# CropSenseMovement_REV03.net
KiCad netlist of a schematic drawn in Altium Designer
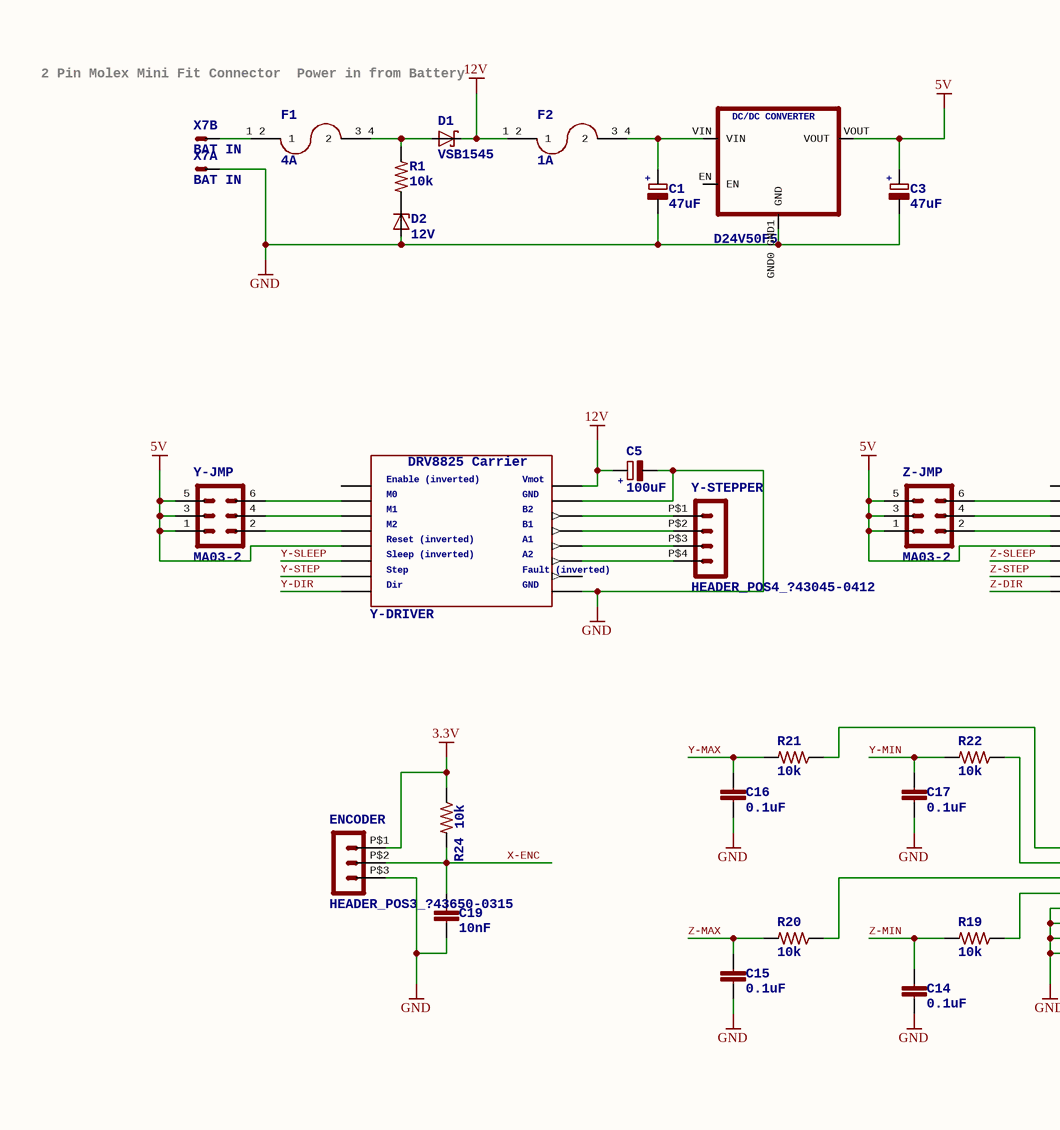
[diagram p0: CropSenseMovement_REV03.SchDoc, left]
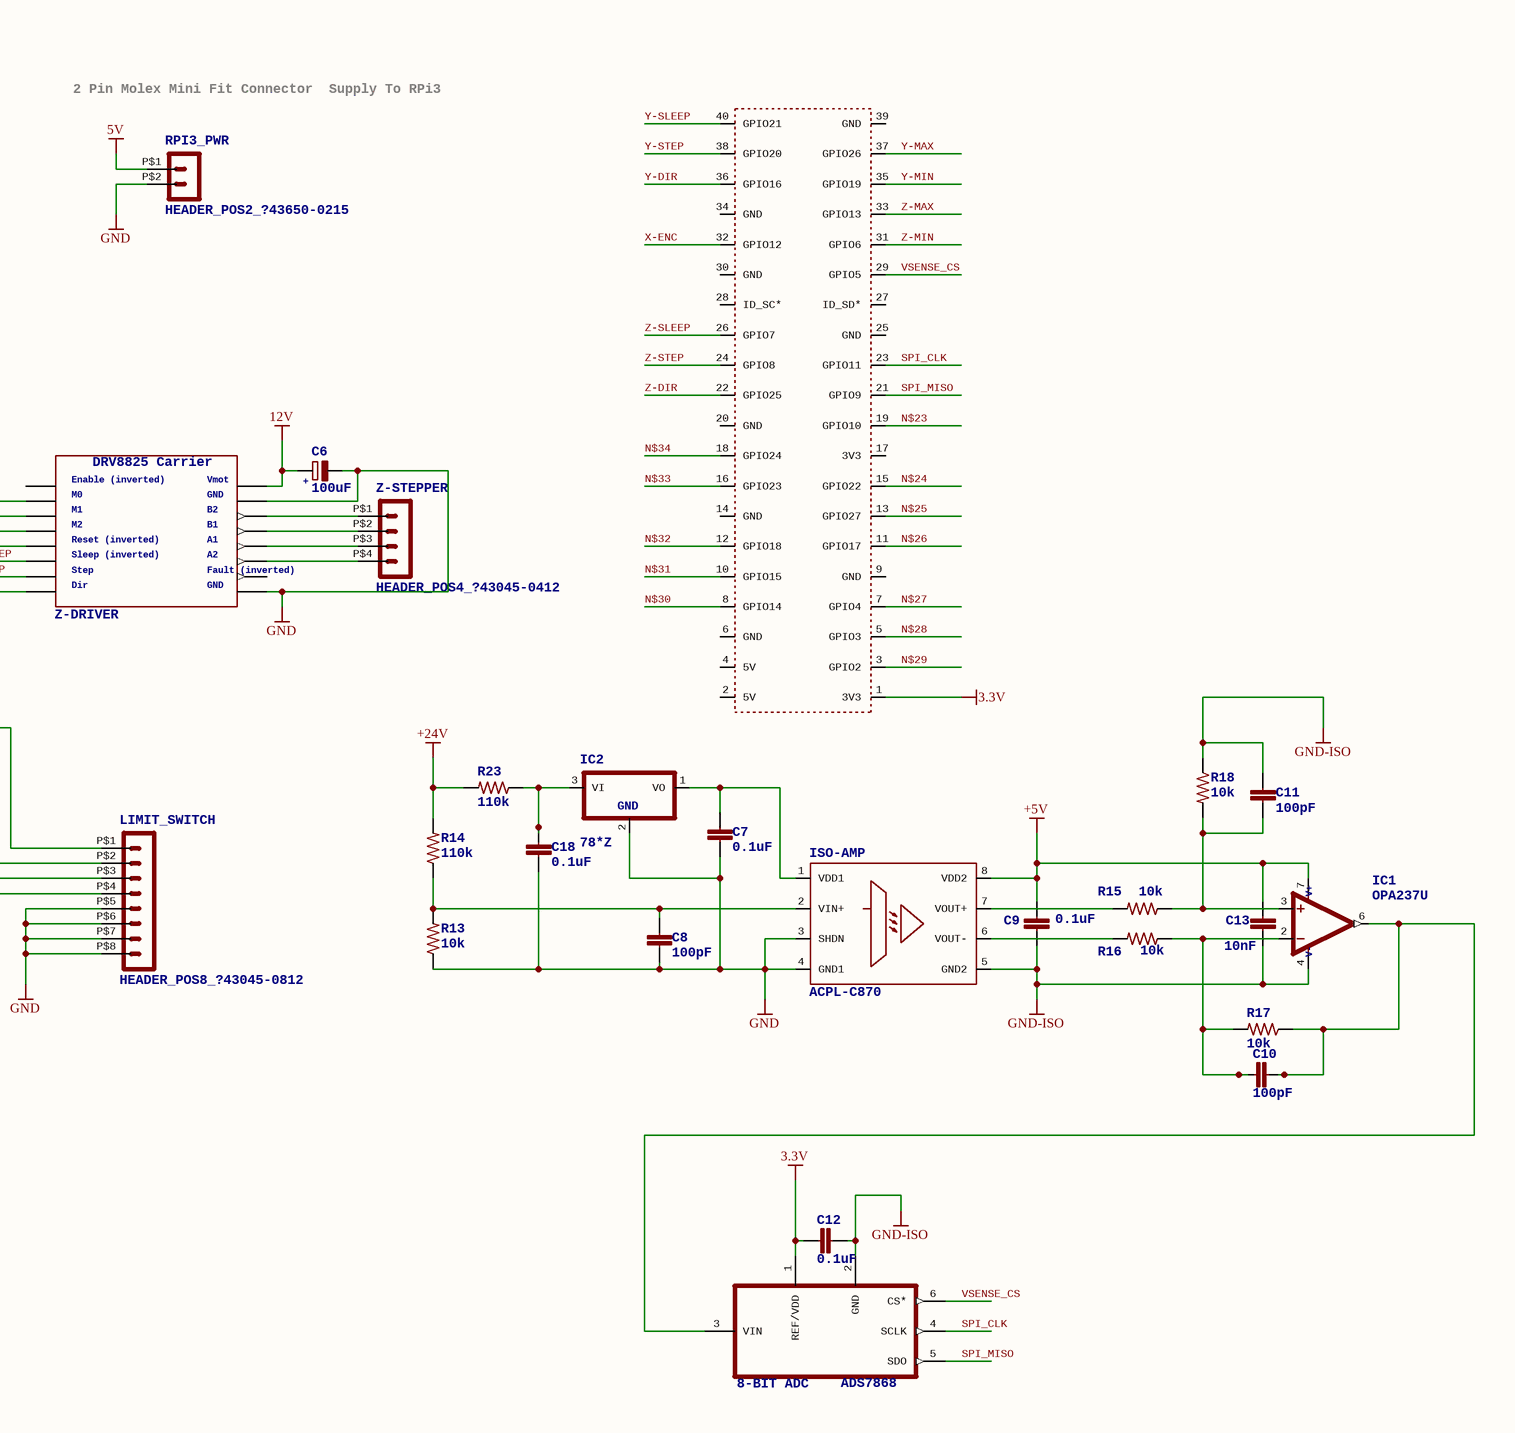
[diagram p1: CropSenseMovement_REV03.SchDoc, right]

(export (version "E")
  (design (tool "Eeschema 10.0.6"))
  (components
    (comp (ref "ADC")
      (value "ADS7868")
      (footprint "SOT-23-6")
      (description "ADS7868    8-bit ADC   Datasheet")
      (fields (field (name "8-BITADC") "8-BIT ADC"))
      (libsource (lib "ADC-BurrBrown") (part "ADS7868"))
    )
    (comp (ref "C1")
      (value "47uF")
      (footprint "E2,5-6")
      (description "POLARIZED CAPACITOR, European symbol")
      (fields (field (name "+") "+"))
      (libsource (lib "rcl") (part "CPOL-EUE2.5-6"))
    )
    (comp (ref "C3")
      (value "47uF")
      (footprint "E2,5-6")
      (description "POLARIZED CAPACITOR, European symbol")
      (fields (field (name "+") "+"))
      (libsource (lib "rcl") (part "CPOL-EUE2.5-6"))
    )
    (comp (ref "C5")
      (value "100uF")
      (footprint "PANASONIC_E")
      (description "POLARIZED CAPACITOR, European symbol")
      (fields (field (name "+") "+"))
      (libsource (lib "rcl") (part "CPOL-EUE"))
    )
    (comp (ref "C6")
      (value "100uF")
      (footprint "PANASONIC_E")
      (description "POLARIZED CAPACITOR, European symbol")
      (fields (field (name "+") "+"))
      (libsource (lib "rcl") (part "CPOL-EUE"))
    )
    (comp (ref "C7")
      (value "0.1uF")
      (footprint "C1206K")
      (description "CAPACITOR, European symbol")
      (libsource (lib "rcl") (part "C-EUC1206K"))
    )
    (comp (ref "C8")
      (value "100pF")
      (footprint "C1206K")
      (description "CAPACITOR, European symbol")
      (libsource (lib "rcl") (part "C-EUC1206K"))
    )
    (comp (ref "C9")
      (value "0.1uF")
      (footprint "C1206K")
      (description "CAPACITOR, European symbol")
      (libsource (lib "rcl") (part "C-EUC1206K"))
    )
    (comp (ref "C10")
      (value "100pF")
      (footprint "C1206K")
      (description "CAPACITOR, European symbol")
      (libsource (lib "") (part "C-EUC1206K_1"))
    )
    (comp (ref "C11")
      (value "100pF")
      (footprint "C1206K")
      (description "CAPACITOR, European symbol")
      (libsource (lib "rcl") (part "C-EUC1206K"))
    )
    (comp (ref "C12")
      (value "0.1uF")
      (footprint "C1206K")
      (description "CAPACITOR, European symbol")
      (libsource (lib "") (part "C-EUC1206K_2"))
    )
    (comp (ref "C13")
      (value "10nF")
      (footprint "C1206K")
      (description "CAPACITOR, European symbol")
      (libsource (lib "rcl") (part "C-EUC1206K"))
    )
    (comp (ref "C14")
      (value "0.1uF")
      (footprint "C1206K")
      (description "CAPACITOR, European symbol")
      (libsource (lib "rcl") (part "C-EUC1206K"))
    )
    (comp (ref "C15")
      (value "0.1uF")
      (footprint "C1206K")
      (description "CAPACITOR, European symbol")
      (libsource (lib "rcl") (part "C-EUC1206K"))
    )
    (comp (ref "C16")
      (value "0.1uF")
      (footprint "C1206K")
      (description "CAPACITOR, European symbol")
      (libsource (lib "rcl") (part "C-EUC1206K"))
    )
    (comp (ref "C17")
      (value "0.1uF")
      (footprint "C1206K")
      (description "CAPACITOR, European symbol")
      (libsource (lib "rcl") (part "C-EUC1206K"))
    )
    (comp (ref "C18")
      (value "0.1uF")
      (footprint "C1206K")
      (description "CAPACITOR, European symbol")
      (libsource (lib "rcl") (part "C-EUC1206K"))
    )
    (comp (ref "C19")
      (value "10nF")
      (footprint "C1206K")
      (description "CAPACITOR, European symbol")
      (libsource (lib "rcl") (part "C-EUC1206K"))
    )
    (comp (ref "D1")
      (value "VSB1545")
      (footprint "P6T15")
      (description "Schottky Diode")
      (libsource (lib "diode") (part "SCHOTTKY-DIODEP6T15"))
    )
    (comp (ref "D2")
      (value "12V")
      (footprint "DO35Z10")
      (description "Z-Diode")
      (libsource (lib "diode") (part "ZENER-DIODEDO35Z10"))
    )
    (comp (ref "ENCODER")
      (value "HEADER_POS3_?43650-0315")
      (footprint "43650-0315")
      (description "Molex - Micro-Fit 3.0 Series connector,  3.00mm (0.118\") pitch header, 3 positions.")
      (libsource (lib "con-molex-micro-fit-3_0") (part "HEADER_POS3_?43650-0315"))
    )
    (comp (ref "F1")
      (value "4A")
      (footprint "5X20MM_LITTLEFUSE_CARTRIDGE")
      (libsource (lib "cs-movement-custom-lib") (part "FUSE_5X20_LITTLEFUSE"))
    )
    (comp (ref "F2")
      (value "1A")
      (footprint "5X20MM_LITTLEFUSE_CARTRIDGE")
      (libsource (lib "cs-movement-custom-lib") (part "FUSE_5X20_LITTLEFUSE"))
    )
    (comp (ref "IC1")
      (value "OPA237U")
      (footprint "SO08")
      (description "Operational Amplifiers   Single-Supply, MicroAmplifier(TM) Series")
      (fields
        (field (name "MF") "TEXAS INSTRUMENT CONNECTORS")
        (field (name "MPN") "OPA237UA")
        (field (name "V+") "V+")
        (field (name "V-") "V-")
      )
      (libsource (lib "burr-brown") (part "OPA237U"))
    )
    (comp (ref "IC2")
      (value "78*Z")
      (footprint "TO92")
      (fields (field (name "GND") "GND"))
      (libsource (lib "linear") (part "78*Z"))
    )
    (comp (ref "ISO-AMP")
      (value "ACPL-C870")
      (footprint "SSO-8")
      (libsource (lib "isolated-amp-avago") (part "ACPL-C870"))
    )
    (comp (ref "LIMIT_SWITCH")
      (value "HEADER_POS8_?43045-0812")
      (footprint "43045-0812")
      (description "Molex - Micro-Fit 3.0 Series connector,  3.00mm (0.118\") pitch header, 8 positions.")
      (libsource (lib "con-molex-micro-fit-3_0") (part "HEADER_POS8_?43045-0812"))
    )
    (comp (ref "R1")
      (value "10k")
      (footprint "R1206")
      (description "RESISTOR, American symbol")
      (libsource (lib "rcl") (part "R-US_R1206"))
    )
    (comp (ref "R13")
      (value "10k")
      (footprint "R1206")
      (description "RESISTOR, American symbol")
      (libsource (lib "rcl") (part "R-US_R1206"))
    )
    (comp (ref "R14")
      (value "110k")
      (footprint "R1206")
      (description "RESISTOR, American symbol")
      (libsource (lib "rcl") (part "R-US_R1206"))
    )
    (comp (ref "R15")
      (value "10k")
      (footprint "R1206")
      (description "RESISTOR, American symbol")
      (libsource (lib "rcl") (part "R-US_R1206"))
    )
    (comp (ref "R16")
      (value "10k")
      (footprint "R1206")
      (description "RESISTOR, American symbol")
      (libsource (lib "rcl") (part "R-US_R1206"))
    )
    (comp (ref "R17")
      (value "10k")
      (footprint "R1206")
      (description "RESISTOR, American symbol")
      (libsource (lib "rcl") (part "R-US_R1206"))
    )
    (comp (ref "R18")
      (value "10k")
      (footprint "R1206")
      (description "RESISTOR, American symbol")
      (libsource (lib "rcl") (part "R-US_R1206"))
    )
    (comp (ref "R19")
      (value "10k")
      (footprint "R1206")
      (description "RESISTOR, American symbol")
      (libsource (lib "rcl") (part "R-US_R1206"))
    )
    (comp (ref "R20")
      (value "10k")
      (footprint "R1206")
      (description "RESISTOR, American symbol")
      (libsource (lib "rcl") (part "R-US_R1206"))
    )
    (comp (ref "R21")
      (value "10k")
      (footprint "R1206")
      (description "RESISTOR, American symbol")
      (libsource (lib "rcl") (part "R-US_R1206"))
    )
    (comp (ref "R22")
      (value "10k")
      (footprint "R1206")
      (description "RESISTOR, American symbol")
      (libsource (lib "rcl") (part "R-US_R1206"))
    )
    (comp (ref "R23")
      (value "110k")
      (footprint "R1206")
      (description "RESISTOR, American symbol")
      (libsource (lib "rcl") (part "R-US_R1206"))
    )
    (comp (ref "R24")
      (value "10k")
      (footprint "R1206")
      (description "RESISTOR, American symbol")
      (libsource (lib "rcl") (part "R-US_R1206"))
    )
    (comp (ref "RPI3_PWR")
      (value "HEADER_POS2_?43650-0215")
      (footprint "43650-0215")
      (description "Molex - Micro-Fit 3.0 Series connector,  3.00mm (0.118\") pitch header, 2 positions.")
      (libsource (lib "con-molex-micro-fit-3_0") (part "HEADER_POS2_?43650-0215"))
    )
    (comp (ref "U$2")
      (value "RPI3_CON")
      (footprint "CONNECTOR")
      (libsource (lib "e14_Rpi3_RevA") (part "RPI3_CON"))
    )
    (comp (ref "U$3")
      (value "D24V50F5")
      (footprint "D24VXXFX_BREAKOUT")
      (fields (field (name "DC/DCCONVERTER") "DC/DC CONVERTER"))
      (libsource (lib "cs-movement-custom-lib") (part "D24V50F5"))
    )
    (comp (ref "X7")
      (value "BAT IN")
      (footprint "5566-2")
      (description "Mini FIT connector 2 pol   Source: http://www.molex.com")
      (libsource (lib "con-molex") (part "5566-2"))
    )
    (comp (ref "Y-DRIVER")
      (value "DRV8825BREAKOUT")
      (footprint "DRV8825BREAKOUT")
      (description "DRV8825 Carrier    Datasheet")
      (fields
        (field (name "GND") "GND")
        (field (name "ENABLE(INVERTED)") "Enable (inverted)")
        (field (name "M0") "M0")
        (field (name "M1") "M1")
        (field (name "M2") "M2")
        (field (name "RESET(INVERTED)") "Reset (inverted)")
        (field (name "SLEEP(INVERTED)") "Sleep (inverted)")
        (field (name "STEP") "Step")
        (field (name "DIR") "Dir")
        (field (name "FAULT(INVERTED)") "Fault (inverted)")
        (field (name "VMOT") "Vmot")
        (field (name "GND_1") "GND")
        (field (name "B2") "B2")
        (field (name "B1") "B1")
        (field (name "A1") "A1")
        (field (name "A2") "A2")
        (field (name "DRV8825CARRIER") "DRV8825 Carrier")
      )
      (libsource (lib "RepRapjr") (part "DRV8825BREAKOUT"))
    )
    (comp (ref "Y-JMP")
      (value "MA03-2")
      (footprint "MA03-2")
      (description "PIN HEADER")
      (libsource (lib "con-lstb") (part "MA03-2"))
    )
    (comp (ref "Y-STEPPER")
      (value "HEADER_POS4_?43045-0412")
      (footprint "43045-0412")
      (description "Molex - Micro-Fit 3.0 Series connector,  3.00mm (0.118\") pitch header, 4 positions.")
      (libsource (lib "con-molex-micro-fit-3_0") (part "HEADER_POS4_?43045-0412"))
    )
    (comp (ref "Z-DRIVER")
      (value "DRV8825BREAKOUT")
      (footprint "DRV8825BREAKOUT")
      (description "DRV8825 Carrier    Datasheet")
      (fields
        (field (name "GND") "GND")
        (field (name "ENABLE(INVERTED)") "Enable (inverted)")
        (field (name "M0") "M0")
        (field (name "M1") "M1")
        (field (name "M2") "M2")
        (field (name "RESET(INVERTED)") "Reset (inverted)")
        (field (name "SLEEP(INVERTED)") "Sleep (inverted)")
        (field (name "STEP") "Step")
        (field (name "DIR") "Dir")
        (field (name "FAULT(INVERTED)") "Fault (inverted)")
        (field (name "VMOT") "Vmot")
        (field (name "GND_1") "GND")
        (field (name "B2") "B2")
        (field (name "B1") "B1")
        (field (name "A1") "A1")
        (field (name "A2") "A2")
        (field (name "DRV8825CARRIER") "DRV8825 Carrier")
      )
      (libsource (lib "RepRapjr") (part "DRV8825BREAKOUT"))
    )
    (comp (ref "Z-JMP")
      (value "MA03-2")
      (footprint "MA03-2")
      (description "PIN HEADER")
      (libsource (lib "con-lstb") (part "MA03-2"))
    )
    (comp (ref "Z-STEPPER")
      (value "HEADER_POS4_?43045-0412")
      (footprint "43045-0412")
      (description "Molex - Micro-Fit 3.0 Series connector,  3.00mm (0.118\") pitch header, 4 positions.")
      (libsource (lib "con-molex-micro-fit-3_0") (part "HEADER_POS4_?43045-0412"))
    )
  )
  (nets
    (net (code "1") (name "+5V") (class "Default")
      (node (ref "C13") (pin "1") (pinfunction "1_1") (pintype "passive"))
      (node (ref "C9") (pin "1") (pinfunction "1_1") (pintype "passive"))
      (node (ref "IC1") (pin "7") (pinfunction "V+_7") (pintype "power_in"))
      (node (ref "ISO-AMP") (pin "8") (pinfunction "VDD2_8") (pintype "power_in"))
    )
    (net (code "2") (name "+24V") (class "Default")
      (node (ref "R14") (pin "2") (pinfunction "2_2") (pintype "passive"))
      (node (ref "R23") (pin "2") (pinfunction "2_2") (pintype "passive"))
    )
    (net (code "3") (name "/N$23") (class "Default")
      (node (ref "U$2") (pin "19") (pinfunction "GPIO10_19") (pintype "passive"))
    )
    (net (code "4") (name "/N$24") (class "Default")
      (node (ref "U$2") (pin "15") (pinfunction "GPIO22_15") (pintype "passive"))
    )
    (net (code "5") (name "/N$25") (class "Default")
      (node (ref "U$2") (pin "13") (pinfunction "GPIO27_13") (pintype "passive"))
    )
    (net (code "6") (name "/N$26") (class "Default")
      (node (ref "U$2") (pin "11") (pinfunction "GPIO17_11") (pintype "passive"))
    )
    (net (code "7") (name "/N$27") (class "Default")
      (node (ref "U$2") (pin "7") (pinfunction "GPIO4_7") (pintype "passive"))
    )
    (net (code "8") (name "/N$28") (class "Default")
      (node (ref "U$2") (pin "5") (pinfunction "GPIO3_5") (pintype "passive"))
    )
    (net (code "9") (name "/N$29") (class "Default")
      (node (ref "U$2") (pin "3") (pinfunction "GPIO2_3") (pintype "passive"))
    )
    (net (code "10") (name "/N$30") (class "Default")
      (node (ref "U$2") (pin "8") (pinfunction "GPIO14_8") (pintype "passive"))
    )
    (net (code "11") (name "/N$31") (class "Default")
      (node (ref "U$2") (pin "10") (pinfunction "GPIO15_10") (pintype "passive"))
    )
    (net (code "12") (name "/N$32") (class "Default")
      (node (ref "U$2") (pin "12") (pinfunction "GPIO18_12") (pintype "passive"))
    )
    (net (code "13") (name "/N$33") (class "Default")
      (node (ref "U$2") (pin "16") (pinfunction "GPIO23_16") (pintype "passive"))
    )
    (net (code "14") (name "/N$34") (class "Default")
      (node (ref "U$2") (pin "18") (pinfunction "GPIO24_18") (pintype "passive"))
    )
    (net (code "15") (name "/SPI_CLK") (class "Default")
      (node (ref "ADC") (pin "4") (pinfunction "SCLK_4") (pintype "output"))
      (node (ref "U$2") (pin "23") (pinfunction "GPIO11_23") (pintype "passive"))
    )
    (net (code "16") (name "/SPI_MISO") (class "Default")
      (node (ref "ADC") (pin "5") (pinfunction "SDO_5") (pintype "output"))
      (node (ref "U$2") (pin "21") (pinfunction "GPIO9_21") (pintype "passive"))
    )
    (net (code "17") (name "/VSENSE_CS") (class "Default")
      (node (ref "ADC") (pin "6") (pinfunction "CS*_6") (pintype "output"))
      (node (ref "U$2") (pin "29") (pinfunction "GPIO5_29") (pintype "passive"))
    )
    (net (code "18") (name "/X-ENC") (class "Default")
      (node (ref "C19") (pin "1") (pinfunction "1_1") (pintype "passive"))
      (node (ref "ENCODER") (pin "P$2") (pinfunction "2_P$2") (pintype "passive"))
      (node (ref "R24") (pin "2") (pinfunction "2_2") (pintype "passive"))
      (node (ref "U$2") (pin "32") (pinfunction "GPIO12_32") (pintype "passive"))
    )
    (net (code "19") (name "/Y-DIR") (class "Default")
      (node (ref "U$2") (pin "36") (pinfunction "GPIO16_36") (pintype "passive"))
      (node (ref "Y-DRIVER") (pin "DIR") (pinfunction "DIR_DIR") (pintype "passive"))
    )
    (net (code "20") (name "/Y-MAX") (class "Default")
      (node (ref "C16") (pin "1") (pinfunction "1_1") (pintype "passive"))
      (node (ref "R21") (pin "2") (pinfunction "2_2") (pintype "passive"))
      (node (ref "U$2") (pin "37") (pinfunction "GPIO26_37") (pintype "passive"))
    )
    (net (code "21") (name "/Y-MIN") (class "Default")
      (node (ref "C17") (pin "1") (pinfunction "1_1") (pintype "passive"))
      (node (ref "R22") (pin "2") (pinfunction "2_2") (pintype "passive"))
      (node (ref "U$2") (pin "35") (pinfunction "GPIO19_35") (pintype "passive"))
    )
    (net (code "22") (name "/Y-SLEEP") (class "Default")
      (node (ref "U$2") (pin "40") (pinfunction "GPIO21_40") (pintype "passive"))
      (node (ref "Y-DRIVER") (pin "SLP") (pinfunction "SLEEP_SLP") (pintype "passive"))
    )
    (net (code "23") (name "/Y-STEP") (class "Default")
      (node (ref "U$2") (pin "38") (pinfunction "GPIO20_38") (pintype "passive"))
      (node (ref "Y-DRIVER") (pin "STEP") (pinfunction "STEP_STEP") (pintype "passive"))
    )
    (net (code "24") (name "/Z-DIR") (class "Default")
      (node (ref "U$2") (pin "22") (pinfunction "GPIO25_22") (pintype "passive"))
      (node (ref "Z-DRIVER") (pin "DIR") (pinfunction "DIR_DIR") (pintype "passive"))
    )
    (net (code "25") (name "/Z-MAX") (class "Default")
      (node (ref "C15") (pin "1") (pinfunction "1_1") (pintype "passive"))
      (node (ref "R20") (pin "2") (pinfunction "2_2") (pintype "passive"))
      (node (ref "U$2") (pin "33") (pinfunction "GPIO13_33") (pintype "passive"))
    )
    (net (code "26") (name "/Z-MIN") (class "Default")
      (node (ref "C14") (pin "1") (pinfunction "1_1") (pintype "passive"))
      (node (ref "R19") (pin "2") (pinfunction "2_2") (pintype "passive"))
      (node (ref "U$2") (pin "31") (pinfunction "GPIO6_31") (pintype "passive"))
    )
    (net (code "27") (name "/Z-SLEEP") (class "Default")
      (node (ref "U$2") (pin "26") (pinfunction "GPIO7_26") (pintype "passive"))
      (node (ref "Z-DRIVER") (pin "SLP") (pinfunction "SLEEP_SLP") (pintype "passive"))
    )
    (net (code "28") (name "/Z-STEP") (class "Default")
      (node (ref "U$2") (pin "24") (pinfunction "GPIO8_24") (pintype "passive"))
      (node (ref "Z-DRIVER") (pin "STEP") (pinfunction "STEP_STEP") (pintype "passive"))
    )
    (net (code "29") (name "3.3V") (class "Default")
      (node (ref "ADC") (pin "1") (pinfunction "REF/VDD_1") (pintype "power_in"))
      (node (ref "C12") (pin "1") (pinfunction "1_1") (pintype "passive"))
      (node (ref "ENCODER") (pin "P$1") (pinfunction "1_P$1") (pintype "passive"))
      (node (ref "R24") (pin "1") (pinfunction "1_1") (pintype "passive"))
      (node (ref "U$2") (pin "1") (pinfunction "3V3_1") (pintype "passive"))
    )
    (net (code "30") (name "5V") (class "Default")
      (node (ref "C3") (pin "+") (pinfunction "+_+") (pintype "passive"))
      (node (ref "RPI3_PWR") (pin "P$1") (pinfunction "1_P$1") (pintype "passive"))
      (node (ref "U$3") (pin "VOUT") (pinfunction "VOUT_VOUT") (pintype "passive"))
      (node (ref "Y-DRIVER") (pin "RST") (pinfunction "RST_RST") (pintype "passive"))
      (node (ref "Y-JMP") (pin "1") (pinfunction "1_1") (pintype "passive"))
      (node (ref "Y-JMP") (pin "3") (pinfunction "3_3") (pintype "passive"))
      (node (ref "Y-JMP") (pin "5") (pinfunction "5_5") (pintype "passive"))
      (node (ref "Z-DRIVER") (pin "RST") (pinfunction "RST_RST") (pintype "passive"))
      (node (ref "Z-JMP") (pin "1") (pinfunction "1_1") (pintype "passive"))
      (node (ref "Z-JMP") (pin "3") (pinfunction "3_3") (pintype "passive"))
      (node (ref "Z-JMP") (pin "5") (pinfunction "5_5") (pintype "passive"))
    )
    (net (code "31") (name "12V") (class "Default")
      (node (ref "C5") (pin "+") (pinfunction "+_+") (pintype "passive"))
      (node (ref "C6") (pin "+") (pinfunction "+_+") (pintype "passive"))
      (node (ref "D1") (pin "C") (pinfunction "C_C") (pintype "passive"))
      (node (ref "F2") (pin "1_2") (pinfunction "1_1_2") (pintype "passive"))
      (node (ref "Y-DRIVER") (pin "VMOT") (pinfunction "VMOT_VMOT") (pintype "power_in"))
      (node (ref "Z-DRIVER") (pin "VMOT") (pinfunction "VMOT_VMOT") (pintype "power_in"))
    )
    (net (code "32") (name "GND") (class "Default")
      (node (ref "C1") (pin "-") (pinfunction "-_-") (pintype "passive"))
      (node (ref "C14") (pin "2") (pinfunction "2_2") (pintype "passive"))
      (node (ref "C15") (pin "2") (pinfunction "2_2") (pintype "passive"))
      (node (ref "C16") (pin "2") (pinfunction "2_2") (pintype "passive"))
      (node (ref "C17") (pin "2") (pinfunction "2_2") (pintype "passive"))
      (node (ref "C18") (pin "2") (pinfunction "2_2") (pintype "passive"))
      (node (ref "C19") (pin "2") (pinfunction "2_2") (pintype "passive"))
      (node (ref "C3") (pin "-") (pinfunction "-_-") (pintype "passive"))
      (node (ref "C5") (pin "-") (pinfunction "-_-") (pintype "passive"))
      (node (ref "C6") (pin "-") (pinfunction "-_-") (pintype "passive"))
      (node (ref "C7") (pin "2") (pinfunction "2_2") (pintype "passive"))
      (node (ref "C8") (pin "2") (pinfunction "2_2") (pintype "passive"))
      (node (ref "D2") (pin "A") (pinfunction "A_A") (pintype "passive"))
      (node (ref "ENCODER") (pin "P$3") (pinfunction "3_P$3") (pintype "passive"))
      (node (ref "IC2") (pin "2") (pinfunction "GND_2") (pintype "passive"))
      (node (ref "ISO-AMP") (pin "3") (pinfunction "SHDN_3") (pintype "power_in"))
      (node (ref "ISO-AMP") (pin "4") (pinfunction "GND1_4") (pintype "power_in"))
      (node (ref "LIMIT_SWITCH") (pin "P$5") (pinfunction "5_P$5") (pintype "passive"))
      (node (ref "LIMIT_SWITCH") (pin "P$6") (pinfunction "6_P$6") (pintype "passive"))
      (node (ref "LIMIT_SWITCH") (pin "P$7") (pinfunction "7_P$7") (pintype "passive"))
      (node (ref "LIMIT_SWITCH") (pin "P$8") (pinfunction "8_P$8") (pintype "passive"))
      (node (ref "R13") (pin "1") (pinfunction "1_1") (pintype "passive"))
      (node (ref "RPI3_PWR") (pin "P$2") (pinfunction "2_P$2") (pintype "passive"))
      (node (ref "U$3") (pin "GND0_GND1") (pinfunction "GND_GND0_GND1") (pintype "passive"))
      (node (ref "X7") (pin "1") (pinfunction "S_1") (pintype "passive"))
      (node (ref "Y-DRIVER") (pin "GND") (pinfunction "GND_GND") (pintype "power_in"))
      (node (ref "Y-DRIVER") (pin "GND0") (pinfunction "GND0_GND0") (pintype "power_in"))
      (node (ref "Z-DRIVER") (pin "GND") (pinfunction "GND_GND") (pintype "power_in"))
      (node (ref "Z-DRIVER") (pin "GND0") (pinfunction "GND0_GND0") (pintype "power_in"))
    )
    (net (code "33") (name "GND-ISO") (class "Default")
      (node (ref "ADC") (pin "2") (pinfunction "GND_2") (pintype "power_in"))
      (node (ref "C11") (pin "1") (pinfunction "1_1") (pintype "passive"))
      (node (ref "C12") (pin "2") (pinfunction "2_2") (pintype "passive"))
      (node (ref "C13") (pin "2") (pinfunction "2_2") (pintype "passive"))
      (node (ref "C9") (pin "2") (pinfunction "2_2") (pintype "passive"))
      (node (ref "IC1") (pin "4") (pinfunction "V-_4") (pintype "power_in"))
      (node (ref "ISO-AMP") (pin "5") (pinfunction "GND2_5") (pintype "power_in"))
      (node (ref "R18") (pin "1") (pinfunction "1_1") (pintype "passive"))
    )
    (net (code "34") (name "Net-(ADC-VIN)") (class "Default")
      (node (ref "ADC") (pin "3") (pinfunction "VIN_3") (pintype "passive"))
      (node (ref "C10") (pin "1") (pinfunction "1_1") (pintype "passive"))
      (node (ref "IC1") (pin "6") (pinfunction "OUT_6") (pintype "output"))
      (node (ref "R17") (pin "1") (pinfunction "1_1") (pintype "passive"))
    )
    (net (code "35") (name "Net-(D2-PadC)") (class "Default")
      (node (ref "D2") (pin "C") (pinfunction "C_C") (pintype "passive"))
      (node (ref "R1") (pin "2") (pinfunction "2_2") (pintype "passive"))
    )
    (net (code "36") (name "Net-(F1-1)") (class "Default")
      (node (ref "F1") (pin "1_2") (pinfunction "1_1_2") (pintype "passive"))
      (node (ref "X7") (pin "2") (pinfunction "S_2") (pintype "passive"))
    )
    (net (code "37") (name "Net-(F1-2)") (class "Default")
      (node (ref "D1") (pin "A") (pinfunction "A_A") (pintype "passive"))
      (node (ref "F1") (pin "3_4") (pinfunction "2_3_4") (pintype "passive"))
      (node (ref "R1") (pin "1") (pinfunction "1_1") (pintype "passive"))
    )
    (net (code "38") (name "Net-(F2-2)") (class "Default")
      (node (ref "C1") (pin "+") (pinfunction "+_+") (pintype "passive"))
      (node (ref "F2") (pin "3_4") (pinfunction "2_3_4") (pintype "passive"))
      (node (ref "U$3") (pin "VIN") (pinfunction "VIN_VIN") (pintype "passive"))
    )
    (net (code "39") (name "Net-(IC1-+IN)") (class "Default")
      (node (ref "C11") (pin "2") (pinfunction "2_2") (pintype "passive"))
      (node (ref "IC1") (pin "3") (pinfunction "+IN_3") (pintype "passive"))
      (node (ref "R15") (pin "1") (pinfunction "1_1") (pintype "passive"))
      (node (ref "R18") (pin "2") (pinfunction "2_2") (pintype "passive"))
    )
    (net (code "40") (name "Net-(IC1--IN)") (class "Default")
      (node (ref "C10") (pin "2") (pinfunction "2_2") (pintype "passive"))
      (node (ref "IC1") (pin "2") (pinfunction "-IN_2") (pintype "passive"))
      (node (ref "R16") (pin "1") (pinfunction "1_1") (pintype "passive"))
      (node (ref "R17") (pin "2") (pinfunction "2_2") (pintype "passive"))
    )
    (net (code "41") (name "Net-(IC2-VI)") (class "Default")
      (node (ref "C18") (pin "1") (pinfunction "1_1") (pintype "passive"))
      (node (ref "IC2") (pin "3") (pinfunction "VI_3") (pintype "passive"))
      (node (ref "R23") (pin "1") (pinfunction "1_1") (pintype "passive"))
    )
    (net (code "42") (name "Net-(IC2-VO)") (class "Default")
      (node (ref "C7") (pin "1") (pinfunction "1_1") (pintype "passive"))
      (node (ref "IC2") (pin "1") (pinfunction "VO_1") (pintype "passive"))
      (node (ref "ISO-AMP") (pin "1") (pinfunction "VDD1_1") (pintype "power_in"))
    )
    (net (code "43") (name "Net-(ISO-AMP-VIN+)") (class "Default")
      (node (ref "C8") (pin "1") (pinfunction "1_1") (pintype "passive"))
      (node (ref "ISO-AMP") (pin "2") (pinfunction "VIN+_2") (pintype "power_in"))
      (node (ref "R13") (pin "2") (pinfunction "2_2") (pintype "passive"))
      (node (ref "R14") (pin "1") (pinfunction "1_1") (pintype "passive"))
    )
    (net (code "44") (name "Net-(ISO-AMP-VOUT+)") (class "Default")
      (node (ref "ISO-AMP") (pin "7") (pinfunction "VOUT+_7") (pintype "power_in"))
      (node (ref "R15") (pin "2") (pinfunction "2_2") (pintype "passive"))
    )
    (net (code "45") (name "Net-(ISO-AMP-VOUT-)") (class "Default")
      (node (ref "ISO-AMP") (pin "6") (pinfunction "VOUT-_6") (pintype "power_in"))
      (node (ref "R16") (pin "2") (pinfunction "2_2") (pintype "passive"))
    )
    (net (code "46") (name "Net-(LIMIT_SWITCH-1)") (class "Default")
      (node (ref "LIMIT_SWITCH") (pin "P$1") (pinfunction "1_P$1") (pintype "passive"))
      (node (ref "R21") (pin "1") (pinfunction "1_1") (pintype "passive"))
    )
    (net (code "47") (name "Net-(LIMIT_SWITCH-2)") (class "Default")
      (node (ref "LIMIT_SWITCH") (pin "P$2") (pinfunction "2_P$2") (pintype "passive"))
      (node (ref "R22") (pin "1") (pinfunction "1_1") (pintype "passive"))
    )
    (net (code "48") (name "Net-(LIMIT_SWITCH-3)") (class "Default")
      (node (ref "LIMIT_SWITCH") (pin "P$3") (pinfunction "3_P$3") (pintype "passive"))
      (node (ref "R20") (pin "1") (pinfunction "1_1") (pintype "passive"))
    )
    (net (code "49") (name "Net-(LIMIT_SWITCH-4)") (class "Default")
      (node (ref "LIMIT_SWITCH") (pin "P$4") (pinfunction "4_P$4") (pintype "passive"))
      (node (ref "R19") (pin "1") (pinfunction "1_1") (pintype "passive"))
    )
    (net (code "50") (name "Net-(Y-DRIVER-PadM0)") (class "Default")
      (node (ref "Y-DRIVER") (pin "M0") (pinfunction "M0_M0") (pintype "passive"))
      (node (ref "Y-JMP") (pin "6") (pinfunction "6_6") (pintype "passive"))
    )
    (net (code "51") (name "Net-(Y-DRIVER-PadM1)") (class "Default")
      (node (ref "Y-DRIVER") (pin "M1") (pinfunction "M1_M1") (pintype "passive"))
      (node (ref "Y-JMP") (pin "4") (pinfunction "4_4") (pintype "passive"))
    )
    (net (code "52") (name "Net-(Y-DRIVER-PadM2)") (class "Default")
      (node (ref "Y-DRIVER") (pin "M2") (pinfunction "M2_M2") (pintype "passive"))
      (node (ref "Y-JMP") (pin "2") (pinfunction "2_2") (pintype "passive"))
    )
    (net (code "53") (name "Net-(Y-STEPPER-1)") (class "Default")
      (node (ref "Y-DRIVER") (pin "B2") (pinfunction "B2_B2") (pintype "output"))
      (node (ref "Y-STEPPER") (pin "P$1") (pinfunction "1_P$1") (pintype "passive"))
    )
    (net (code "54") (name "Net-(Y-STEPPER-2)") (class "Default")
      (node (ref "Y-DRIVER") (pin "B1") (pinfunction "B1_B1") (pintype "output"))
      (node (ref "Y-STEPPER") (pin "P$2") (pinfunction "2_P$2") (pintype "passive"))
    )
    (net (code "55") (name "Net-(Y-STEPPER-3)") (class "Default")
      (node (ref "Y-DRIVER") (pin "A1") (pinfunction "A1_A1") (pintype "output"))
      (node (ref "Y-STEPPER") (pin "P$3") (pinfunction "3_P$3") (pintype "passive"))
    )
    (net (code "56") (name "Net-(Y-STEPPER-4)") (class "Default")
      (node (ref "Y-DRIVER") (pin "A2") (pinfunction "A2_A2") (pintype "output"))
      (node (ref "Y-STEPPER") (pin "P$4") (pinfunction "4_P$4") (pintype "passive"))
    )
    (net (code "57") (name "Net-(Z-DRIVER-PadM0)") (class "Default")
      (node (ref "Z-DRIVER") (pin "M0") (pinfunction "M0_M0") (pintype "passive"))
      (node (ref "Z-JMP") (pin "6") (pinfunction "6_6") (pintype "passive"))
    )
    (net (code "58") (name "Net-(Z-DRIVER-PadM1)") (class "Default")
      (node (ref "Z-DRIVER") (pin "M1") (pinfunction "M1_M1") (pintype "passive"))
      (node (ref "Z-JMP") (pin "4") (pinfunction "4_4") (pintype "passive"))
    )
    (net (code "59") (name "Net-(Z-DRIVER-PadM2)") (class "Default")
      (node (ref "Z-DRIVER") (pin "M2") (pinfunction "M2_M2") (pintype "passive"))
      (node (ref "Z-JMP") (pin "2") (pinfunction "2_2") (pintype "passive"))
    )
    (net (code "60") (name "Net-(Z-STEPPER-1)") (class "Default")
      (node (ref "Z-DRIVER") (pin "B2") (pinfunction "B2_B2") (pintype "output"))
      (node (ref "Z-STEPPER") (pin "P$1") (pinfunction "1_P$1") (pintype "passive"))
    )
    (net (code "61") (name "Net-(Z-STEPPER-2)") (class "Default")
      (node (ref "Z-DRIVER") (pin "B1") (pinfunction "B1_B1") (pintype "output"))
      (node (ref "Z-STEPPER") (pin "P$2") (pinfunction "2_P$2") (pintype "passive"))
    )
    (net (code "62") (name "Net-(Z-STEPPER-3)") (class "Default")
      (node (ref "Z-DRIVER") (pin "A1") (pinfunction "A1_A1") (pintype "output"))
      (node (ref "Z-STEPPER") (pin "P$3") (pinfunction "3_P$3") (pintype "passive"))
    )
    (net (code "63") (name "Net-(Z-STEPPER-4)") (class "Default")
      (node (ref "Z-DRIVER") (pin "A2") (pinfunction "A2_A2") (pintype "output"))
      (node (ref "Z-STEPPER") (pin "P$4") (pinfunction "4_P$4") (pintype "passive"))
    )
    (net (code "64") (name "unconnected-(U$2-3V3-Pad17)") (class "Default")
      (node (ref "U$2") (pin "17") (pinfunction "3V3_17") (pintype "passive"))
    )
    (net (code "65") (name "unconnected-(U$2-5V-Pad2)") (class "Default")
      (node (ref "U$2") (pin "2") (pinfunction "5V_2") (pintype "passive"))
    )
    (net (code "66") (name "unconnected-(U$2-5V-Pad4)") (class "Default")
      (node (ref "U$2") (pin "4") (pinfunction "5V_4") (pintype "passive"))
    )
    (net (code "67") (name "unconnected-(U$2-GND-Pad6)") (class "Default")
      (node (ref "U$2") (pin "6") (pinfunction "GND_6") (pintype "passive"))
    )
    (net (code "68") (name "unconnected-(U$2-GND-Pad9)") (class "Default")
      (node (ref "U$2") (pin "9") (pinfunction "GND_9") (pintype "passive"))
    )
    (net (code "69") (name "unconnected-(U$2-GND-Pad14)") (class "Default")
      (node (ref "U$2") (pin "14") (pinfunction "GND_14") (pintype "passive"))
    )
    (net (code "70") (name "unconnected-(U$2-GND-Pad20)") (class "Default")
      (node (ref "U$2") (pin "20") (pinfunction "GND_20") (pintype "passive"))
    )
    (net (code "71") (name "unconnected-(U$2-GND-Pad25)") (class "Default")
      (node (ref "U$2") (pin "25") (pinfunction "GND_25") (pintype "passive"))
    )
    (net (code "72") (name "unconnected-(U$2-GND-Pad30)") (class "Default")
      (node (ref "U$2") (pin "30") (pinfunction "GND_30") (pintype "passive"))
    )
    (net (code "73") (name "unconnected-(U$2-GND-Pad34)") (class "Default")
      (node (ref "U$2") (pin "34") (pinfunction "GND_34") (pintype "passive"))
    )
    (net (code "74") (name "unconnected-(U$2-GND-Pad39)") (class "Default")
      (node (ref "U$2") (pin "39") (pinfunction "GND_39") (pintype "passive"))
    )
    (net (code "75") (name "unconnected-(U$2-ID_SC*-Pad28)") (class "Default")
      (node (ref "U$2") (pin "28") (pinfunction "ID_SC*_28") (pintype "passive"))
    )
    (net (code "76") (name "unconnected-(U$2-ID_SD*-Pad27)") (class "Default")
      (node (ref "U$2") (pin "27") (pinfunction "ID_SD*_27") (pintype "passive"))
    )
    (net (code "77") (name "unconnected-(U$3-PadEN)") (class "Default")
      (node (ref "U$3") (pin "EN") (pinfunction "EN_EN") (pintype "passive"))
    )
    (net (code "78") (name "unconnected-(Y-DRIVER-PadEN)") (class "Default")
      (node (ref "Y-DRIVER") (pin "EN") (pinfunction "EN_EN") (pintype "passive"))
    )
    (net (code "79") (name "unconnected-(Y-DRIVER-PadFAULT)") (class "Default")
      (node (ref "Y-DRIVER") (pin "FAULT") (pinfunction "FAULT_FAULT") (pintype "output"))
    )
    (net (code "80") (name "unconnected-(Z-DRIVER-PadEN)") (class "Default")
      (node (ref "Z-DRIVER") (pin "EN") (pinfunction "EN_EN") (pintype "passive"))
    )
    (net (code "81") (name "unconnected-(Z-DRIVER-PadFAULT)") (class "Default")
      (node (ref "Z-DRIVER") (pin "FAULT") (pinfunction "FAULT_FAULT") (pintype "output"))
    )
  )
)
